# Power.net
KiCad netlist of a schematic drawn in Altium Designer
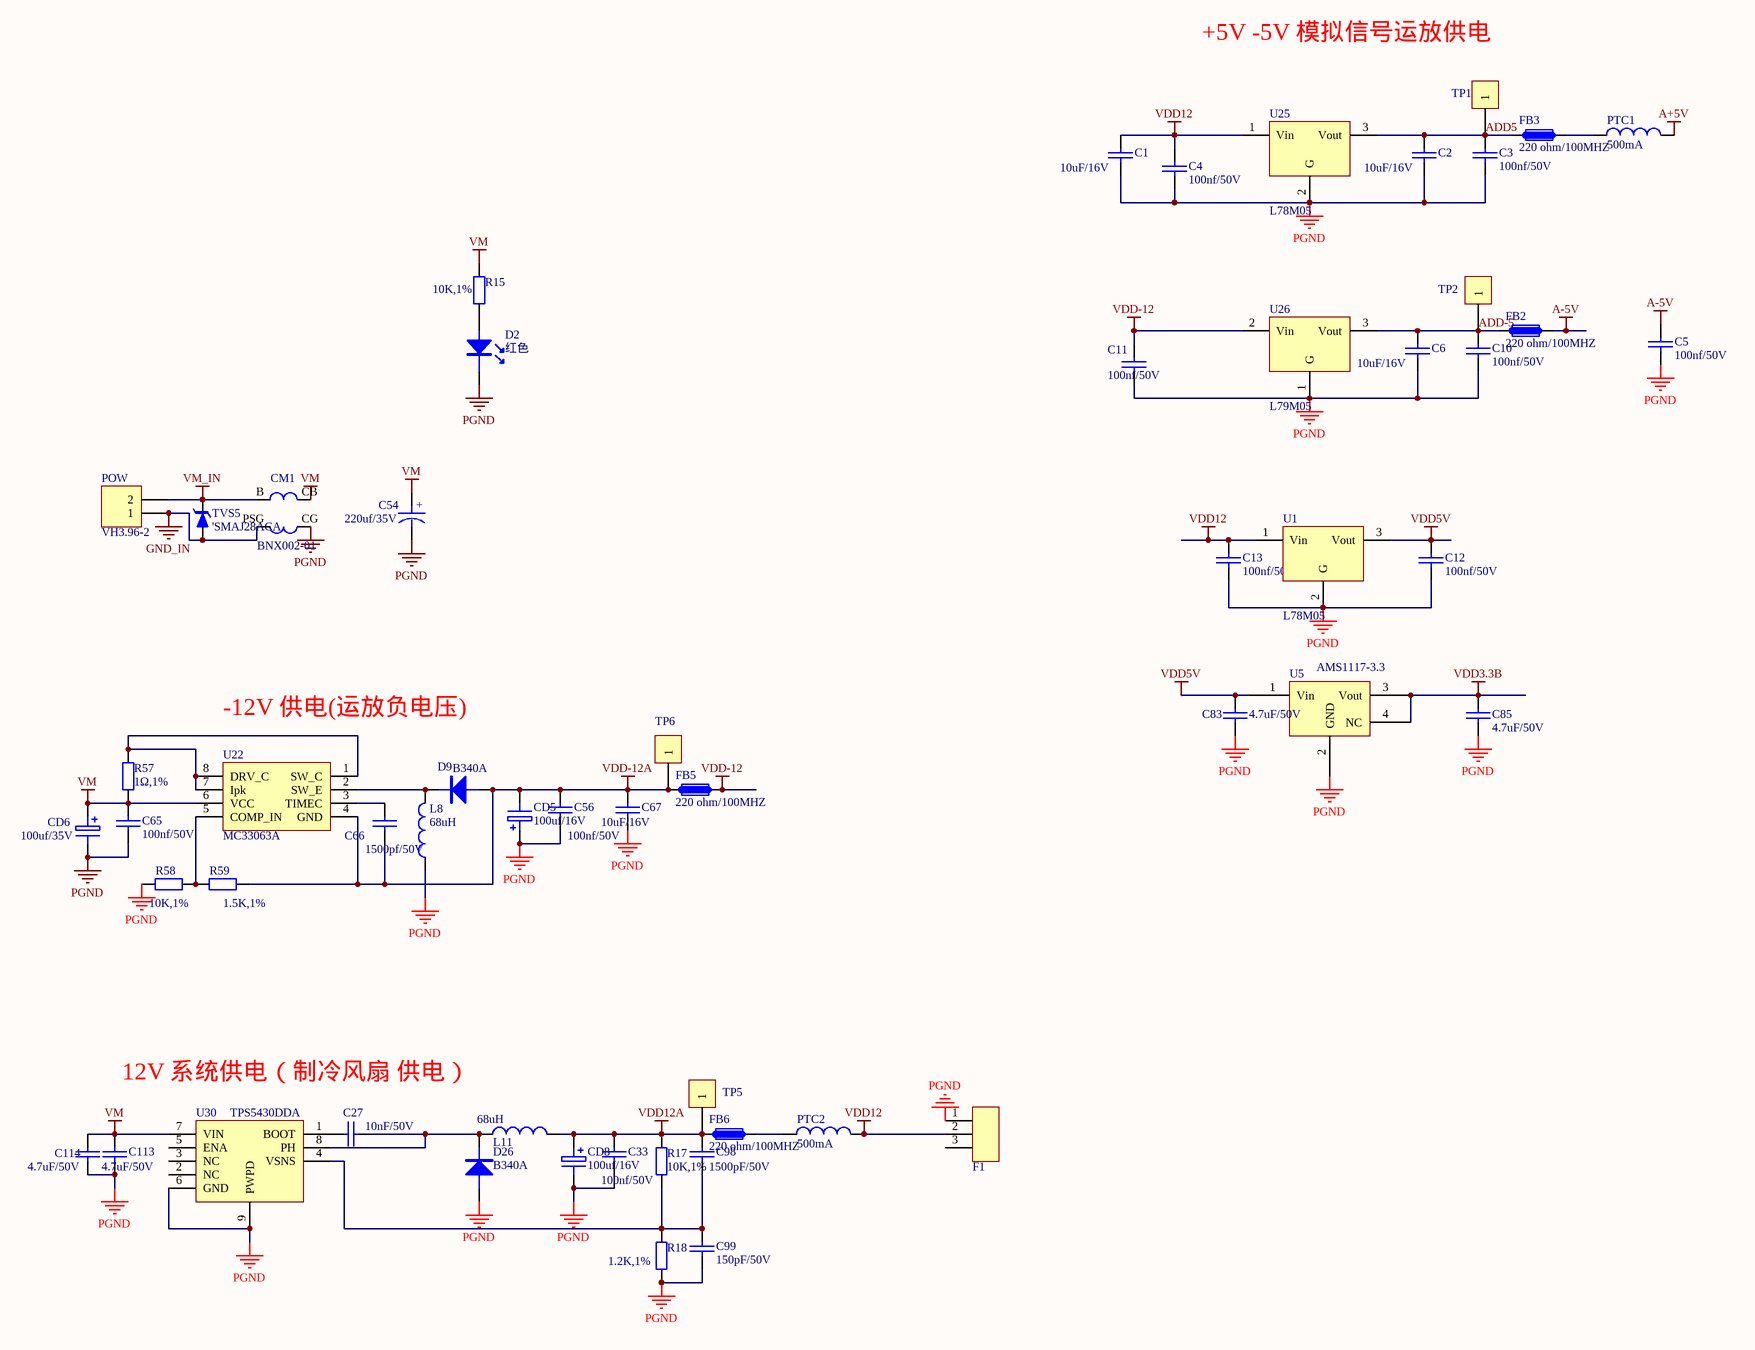
[diagram p0: Power.SchDoc]

(export (version "E")
  (design (tool "Eeschema 10.0.6"))
  (components
    (comp (ref "C1")
      (value "10uF/16V")
      (footprint "1206")
      (description "Capacitor")
      (libsource (lib "DiscreteCom") (part "CAP"))
    )
    (comp (ref "C2")
      (value "10uF/16V")
      (footprint "1206")
      (description "Capacitor")
      (libsource (lib "DiscreteCom") (part "CAP"))
    )
    (comp (ref "C3")
      (value "100nf/50V")
      (footprint "0805")
      (description "Capacitor")
      (libsource (lib "*") (part "CAP"))
    )
    (comp (ref "C4")
      (value "100nf/50V")
      (footprint "0805")
      (description "Capacitor")
      (libsource (lib "*") (part "CAP"))
    )
    (comp (ref "C5")
      (value "100nf/50V")
      (footprint "GeneralPcblib V0.1:0805")
      (description "Capacitor")
      (libsource (lib "General") (part "CAP"))
    )
    (comp (ref "C6")
      (value "10uF/16V")
      (footprint "1206")
      (description "Capacitor")
      (libsource (lib "DiscreteCom") (part "CAP"))
    )
    (comp (ref "C10")
      (value "100nf/50V")
      (footprint "0805")
      (description "Capacitor")
      (libsource (lib "*") (part "CAP"))
    )
    (comp (ref "C11")
      (value "100nf/50V")
      (footprint "0805")
      (description "Capacitor")
      (libsource (lib "*") (part "CAP"))
    )
    (comp (ref "C12")
      (value "100nf/50V")
      (footprint "0805")
      (description "Capacitor")
      (libsource (lib "*") (part "CAP"))
    )
    (comp (ref "C13")
      (value "100nf/50V")
      (footprint "0805")
      (description "Capacitor")
      (libsource (lib "*") (part "CAP"))
    )
    (comp (ref "C27")
      (value "10nF/50V")
      (footprint "0805")
      (description "Capacitor")
      (libsource (lib "DiscreteCom") (part "CAP"))
    )
    (comp (ref "C33")
      (value "100nf/50V")
      (footprint "0805")
      (description "Capacitor")
      (libsource (lib "DiscreteCom") (part "CAP"))
    )
    (comp (ref "C54")
      (value "220uf/35V")
      (footprint "CX8*10.5")
      (description "Capacitor")
      (libsource (lib "General") (part "CAPACITOR POL"))
    )
    (comp (ref "C56")
      (value "100nf/50V")
      (footprint "0805")
      (description "Capacitor")
      (libsource (lib "DiscreteCom") (part "CAP"))
    )
    (comp (ref "C65")
      (value "100nf/50V")
      (footprint "0805")
      (description "Capacitor")
      (libsource (lib "DiscreteCom") (part "CAP"))
    )
    (comp (ref "C66")
      (value "1500pf/50V")
      (footprint "0805")
      (description "Capacitor")
      (libsource (lib "DiscreteCom") (part "CAP"))
    )
    (comp (ref "C67")
      (value "10uF/16V")
      (footprint "GeneralPcblib V0.1:1206")
      (description "Capacitor")
      (libsource (lib "General") (part "CAP"))
    )
    (comp (ref "C83")
      (value "4.7uF/50V")
      (footprint "1206")
      (description "Capacitor")
      (libsource (lib "DiscreteCom") (part "CAP"))
    )
    (comp (ref "C85")
      (value "4.7uF/50V")
      (footprint "1206")
      (description "Capacitor")
      (libsource (lib "DiscreteCom") (part "CAP"))
    )
    (comp (ref "C98")
      (value "1500pF/50V")
      (footprint "0805")
      (description "Capacitor")
      (libsource (lib "DiscreteCom") (part "CAP"))
    )
    (comp (ref "C99")
      (value "150pF/50V")
      (footprint "0805")
      (description "Capacitor")
      (libsource (lib "DiscreteCom") (part "CAP"))
    )
    (comp (ref "C113")
      (value "4.7uF/50V")
      (footprint "1206")
      (description "Capacitor")
      (libsource (lib "DiscreteCom") (part "CAP"))
    )
    (comp (ref "C114")
      (value "4.7uF/50V")
      (footprint "1206")
      (description "Capacitor")
      (libsource (lib "DiscreteCom") (part "CAP"))
    )
    (comp (ref "CD5")
      (value "100uf/16V")
      (footprint "7343D")
      (description "Electrolytic Capacitor")
      (libsource (lib "DiscreteCom") (part "Capacitor Electrolytic"))
    )
    (comp (ref "CD6")
      (value "100uf/35V")
      (footprint "CX6.3*5.4")
      (description "Electrolytic Capacitor")
      (libsource (lib "DiscreteCom") (part "Capacitor Electrolytic"))
    )
    (comp (ref "CD8")
      (value "100uf/16V")
      (footprint "7343D")
      (description "Electrolytic Capacitor")
      (libsource (lib "DiscreteCom") (part "Capacitor Electrolytic"))
    )
    (comp (ref "CM1")
      (value "BNX002-01")
      (footprint "GeneralPcblib V0.1:BNX-002-01")
      (description "inductor")
      (libsource (lib "DiscreteCom") (part "EMIFIL-BNX"))
    )
    (comp (ref "D2")
      (value "红色")
      (footprint "LED_0805")
      (description "Led")
      (fields (field (name "Comment") "LED,Red"))
      (libsource (lib "DiscreteCom") (part "LED"))
    )
    (comp (ref "D9")
      (value "B340A")
      (footprint "SMA")
      (description "Diode")
      (libsource (lib "General") (part "DIODE"))
    )
    (comp (ref "D26")
      (value "B340A")
      (footprint "SMA")
      (description "Diode")
      (libsource (lib "General") (part "DIODE"))
    )
    (comp (ref "F1")
      (value "KF2510-3P")
      (footprint "KF2510-3")
      (description "KF2510-2.54-3P 针座")
      (libsource (lib "CON1") (part "KF2510-3P"))
    )
    (comp (ref "FB2")
      (value "220 ohm/100MHZ")
      (footprint "0805")
      (description "Ferrite Bead")
      (libsource (lib "DiscreteCom") (part "Ferrite Bead"))
    )
    (comp (ref "FB3")
      (value "220 ohm/100MHZ")
      (footprint "0805")
      (description "Ferrite Bead")
      (libsource (lib "DiscreteCom") (part "Ferrite Bead"))
    )
    (comp (ref "FB5")
      (value "220 ohm/100MHZ")
      (footprint "0805")
      (description "Ferrite Bead")
      (libsource (lib "DiscreteCom") (part "Ferrite Bead"))
    )
    (comp (ref "FB6")
      (value "220 ohm/100MHZ")
      (footprint "0805")
      (description "Ferrite Bead")
      (libsource (lib "DiscreteCom") (part "Ferrite Bead"))
    )
    (comp (ref "L8")
      (value "68uH")
      (footprint "INDUCTOR 6*6")
      (description "Inductor")
      (libsource (lib "General") (part "INDUCTOR"))
    )
    (comp (ref "L11")
      (value "68uH")
      (footprint "INDUCTOR 6*6")
      (description "Inductor")
      (libsource (lib "General") (part "INDUCTOR"))
    )
    (comp (ref "POW")
      (value "VH3.96-2")
      (footprint "VH3.96-2")
      (description "VH3.96 2P 插座")
      (fields (field (name "PUBLISHER") "Altium Limited"))
      (libsource (lib "CON1") (part "VH-2"))
    )
    (comp (ref "PTC1")
      (value "500mA")
      (footprint "GeneralPcblib V0.1:1210")
      (description "PTCC")
      (libsource (lib "DiscreteCom") (part "PTCC"))
    )
    (comp (ref "PTC2")
      (value "500mA")
      (footprint "GeneralPcblib V0.1:1210")
      (description "PTCC")
      (libsource (lib "DiscreteCom") (part "PTCC"))
    )
    (comp (ref "R15")
      (value "10K,1%")
      (footprint "0805")
      (description "Resistor")
      (fields (field (name "PUBLISHER") "Altium Limited"))
      (libsource (lib "") (part "Res2_2"))
    )
    (comp (ref "R17")
      (value "10K,1%")
      (footprint "0805")
      (description "Resistor")
      (fields (field (name "PUBLISHER") "Altium Limited"))
      (libsource (lib "General") (part "Res2"))
    )
    (comp (ref "R18")
      (value "1.2K,1%")
      (footprint "0805")
      (description "Resistor")
      (fields (field (name "PUBLISHER") "Altium Limited"))
      (libsource (lib "General") (part "Res2"))
    )
    (comp (ref "R57")
      (value "1Ω,1%")
      (footprint "GeneralPcblib V0.1:2512")
      (description "Resistor")
      (fields (field (name "PUBLISHER") "Altium Limited"))
      (libsource (lib "") (part "Res2_2"))
    )
    (comp (ref "R58")
      (value "10K,1%")
      (footprint "0805")
      (description "Resistor")
      (fields (field (name "PUBLISHER") "Altium Limited"))
      (libsource (lib "") (part "Res2_1"))
    )
    (comp (ref "R59")
      (value "1.5K,1%")
      (footprint "0805")
      (description "Resistor")
      (fields (field (name "PUBLISHER") "Altium Limited"))
      (libsource (lib "") (part "Res2_1"))
    )
    (comp (ref "TP1")
      (value "TP")
      (footprint "TP1")
      (description "Connector")
      (libsource (lib "General") (part "TP"))
    )
    (comp (ref "TP2")
      (value "TP")
      (footprint "TP1")
      (description "Connector")
      (libsource (lib "General") (part "TP"))
    )
    (comp (ref "TP5")
      (value "TP")
      (footprint "TP1")
      (description "Connector")
      (libsource (lib "General") (part "TP"))
    )
    (comp (ref "TP6")
      (value "TP")
      (footprint "TP1")
      (description "Connector")
      (libsource (lib "General") (part "TP"))
    )
    (comp (ref "TVS5")
      (value "'SMAJ28ACA")
      (footprint "GeneralPcblib V0.1:SMB")
      (libsource (lib "DiscreteCom") (part "TVS"))
    )
    (comp (ref "U1")
      (value "L78M05")
      (footprint "TO-252")
      (description "L78XX系列芯片")
      (libsource (lib "AnalogIC") (part "L78XX"))
    )
    (comp (ref "U5")
      (value "AMS1117-3.3")
      (footprint "SOT223S")
      (libsource (lib "General") (part "LM1117-33"))
    )
    (comp (ref "U22") (value "MC33063A") (footprint "SOIC8") (libsource (lib "General") (part "MC33063A")))
    (comp (ref "U25")
      (value "L78M05")
      (footprint "TO-252")
      (description "L78XX系列芯片")
      (libsource (lib "AnalogIC") (part "L78XX"))
    )
    (comp (ref "U26")
      (value "L79M05")
      (footprint "TO-252")
      (description "L79XX系列芯片")
      (libsource (lib "AnalogIC") (part "L79XX"))
    )
    (comp (ref "U30")
      (value "TPS5430DDA")
      (footprint "S0IC8-DDA")
      (libsource (lib "General") (part "TPS5430DDA"))
    )
  )
  (nets
    (net (code "1") (name "/ADD-5") (class "Default")
      (node (ref "C10") (pin "1") (pinfunction "1_1") (pintype "passive"))
      (node (ref "C6") (pin "1") (pinfunction "1_1") (pintype "passive"))
      (node (ref "FB2") (pin "1") (pinfunction "1_1") (pintype "passive"))
      (node (ref "TP2") (pin "1") (pinfunction "1_1") (pintype "passive"))
      (node (ref "U26") (pin "3") (pinfunction "Vout_3") (pintype "passive"))
    )
    (net (code "2") (name "/ADD5") (class "Default")
      (node (ref "C2") (pin "1") (pinfunction "1_1") (pintype "passive"))
      (node (ref "C3") (pin "1") (pinfunction "1_1") (pintype "passive"))
      (node (ref "FB3") (pin "1") (pinfunction "1_1") (pintype "passive"))
      (node (ref "TP1") (pin "1") (pinfunction "1_1") (pintype "passive"))
      (node (ref "U25") (pin "3") (pinfunction "Vout_3") (pintype "passive"))
    )
    (net (code "3") (name "A+5V") (class "Default")
      (node (ref "PTC1") (pin "2") (pinfunction "2_2") (pintype "passive"))
    )
    (net (code "4") (name "A-5V") (class "Default")
      (node (ref "C5") (pin "1") (pinfunction "1_1") (pintype "passive"))
      (node (ref "FB2") (pin "2") (pinfunction "2_2") (pintype "passive"))
    )
    (net (code "5") (name "GND_IN") (class "Default")
      (node (ref "CM1") (pin "PSG") (pinfunction "PSG_PSG") (pintype "passive"))
      (node (ref "POW") (pin "1") (pinfunction "1_1") (pintype "passive"))
      (node (ref "TVS5") (pin "A") (pinfunction "A_A") (pintype "passive"))
    )
    (net (code "6") (name "Net-(D2-PadA)") (class "Default")
      (node (ref "D2") (pin "A") (pinfunction "A_A") (pintype "passive"))
      (node (ref "R15") (pin "2") (pinfunction "2_2") (pintype "passive"))
    )
    (net (code "7") (name "Net-(FB3-Pad2)") (class "Default")
      (node (ref "FB3") (pin "2") (pinfunction "2_2") (pintype "passive"))
      (node (ref "PTC1") (pin "1") (pinfunction "1_1") (pintype "passive"))
    )
    (net (code "8") (name "Net-(FB6-Pad2)") (class "Default")
      (node (ref "FB6") (pin "2") (pinfunction "2_2") (pintype "passive"))
      (node (ref "PTC2") (pin "1") (pinfunction "1_1") (pintype "passive"))
    )
    (net (code "9") (name "Net-(U22-COMP_IN)") (class "Default")
      (node (ref "R58") (pin "1") (pinfunction "1_1") (pintype "passive"))
      (node (ref "R59") (pin "2") (pinfunction "2_2") (pintype "passive"))
      (node (ref "U22") (pin "5") (pinfunction "COMP_IN_5") (pintype "passive"))
    )
    (net (code "10") (name "Net-(U22-DRV_C)") (class "Default")
      (node (ref "R57") (pin "1") (pinfunction "1_1") (pintype "passive"))
      (node (ref "U22") (pin "1") (pinfunction "SW_C_1") (pintype "passive"))
      (node (ref "U22") (pin "7") (pinfunction "Ipk_7") (pintype "passive"))
      (node (ref "U22") (pin "8") (pinfunction "DRV_C_8") (pintype "passive"))
    )
    (net (code "11") (name "Net-(U22-SW_E)") (class "Default")
      (node (ref "D9") (pin "K") (pinfunction "K_K") (pintype "passive"))
      (node (ref "L8") (pin "2") (pinfunction "2_2") (pintype "passive"))
      (node (ref "U22") (pin "2") (pinfunction "SW_E_2") (pintype "passive"))
    )
    (net (code "12") (name "Net-(U22-TIMEC)") (class "Default")
      (node (ref "C66") (pin "1") (pinfunction "1_1") (pintype "passive"))
      (node (ref "U22") (pin "3") (pinfunction "TIMEC_3") (pintype "passive"))
    )
    (net (code "13") (name "Net-(U30-BOOT)") (class "Default")
      (node (ref "C27") (pin "1") (pinfunction "1_1") (pintype "passive"))
      (node (ref "U30") (pin "1") (pinfunction "BOOT_1") (pintype "passive"))
    )
    (net (code "14") (name "Net-(U30-PH)") (class "Default")
      (node (ref "C27") (pin "2") (pinfunction "2_2") (pintype "passive"))
      (node (ref "D26") (pin "K") (pinfunction "K_K") (pintype "passive"))
      (node (ref "L11") (pin "1") (pinfunction "1_1") (pintype "passive"))
      (node (ref "U30") (pin "8") (pinfunction "PH_8") (pintype "passive"))
    )
    (net (code "15") (name "Net-(U30-VSNS)") (class "Default")
      (node (ref "C98") (pin "1") (pinfunction "1_1") (pintype "passive"))
      (node (ref "C99") (pin "2") (pinfunction "2_2") (pintype "passive"))
      (node (ref "R17") (pin "1") (pinfunction "1_1") (pintype "passive"))
      (node (ref "R18") (pin "2") (pinfunction "2_2") (pintype "passive"))
      (node (ref "U30") (pin "4") (pinfunction "VSNS_4") (pintype "passive"))
    )
    (net (code "16") (name "PGND") (class "Default")
      (node (ref "C1") (pin "2") (pinfunction "2_2") (pintype "passive"))
      (node (ref "C10") (pin "2") (pinfunction "2_2") (pintype "passive"))
      (node (ref "C11") (pin "2") (pinfunction "2_2") (pintype "passive"))
      (node (ref "C113") (pin "2") (pinfunction "2_2") (pintype "passive"))
      (node (ref "C114") (pin "2") (pinfunction "2_2") (pintype "passive"))
      (node (ref "C12") (pin "2") (pinfunction "2_2") (pintype "passive"))
      (node (ref "C13") (pin "2") (pinfunction "2_2") (pintype "passive"))
      (node (ref "C2") (pin "2") (pinfunction "2_2") (pintype "passive"))
      (node (ref "C3") (pin "2") (pinfunction "2_2") (pintype "passive"))
      (node (ref "C33") (pin "2") (pinfunction "2_2") (pintype "passive"))
      (node (ref "C4") (pin "2") (pinfunction "2_2") (pintype "passive"))
      (node (ref "C5") (pin "2") (pinfunction "2_2") (pintype "passive"))
      (node (ref "C54") (pin "2") (pinfunction "2_2") (pintype "passive"))
      (node (ref "C56") (pin "2") (pinfunction "2_2") (pintype "passive"))
      (node (ref "C6") (pin "2") (pinfunction "2_2") (pintype "passive"))
      (node (ref "C65") (pin "2") (pinfunction "2_2") (pintype "passive"))
      (node (ref "C67") (pin "2") (pinfunction "2_2") (pintype "passive"))
      (node (ref "C83") (pin "2") (pinfunction "2_2") (pintype "passive"))
      (node (ref "C85") (pin "2") (pinfunction "2_2") (pintype "passive"))
      (node (ref "C99") (pin "1") (pinfunction "1_1") (pintype "passive"))
      (node (ref "CD5") (pin "1") (pinfunction "1_1") (pintype "passive"))
      (node (ref "CD6") (pin "2") (pinfunction "2_2") (pintype "passive"))
      (node (ref "CD8") (pin "2") (pinfunction "2_2") (pintype "passive"))
      (node (ref "CM1") (pin "CG") (pinfunction "CG_CG") (pintype "passive"))
      (node (ref "D2") (pin "K") (pinfunction "K_K") (pintype "passive"))
      (node (ref "D26") (pin "A") (pinfunction "A_A") (pintype "passive"))
      (node (ref "F1") (pin "1") (pintype "passive"))
      (node (ref "L8") (pin "1") (pinfunction "1_1") (pintype "passive"))
      (node (ref "R18") (pin "1") (pinfunction "1_1") (pintype "passive"))
      (node (ref "R58") (pin "2") (pinfunction "2_2") (pintype "passive"))
      (node (ref "U1") (pin "2") (pinfunction "G_2") (pintype "passive"))
      (node (ref "U25") (pin "2") (pinfunction "G_2") (pintype "passive"))
      (node (ref "U26") (pin "1") (pinfunction "G_1") (pintype "passive"))
      (node (ref "U30") (pin "6") (pinfunction "GND_6") (pintype "passive"))
      (node (ref "U30") (pin "9") (pinfunction "PWPD_9") (pintype "passive"))
      (node (ref "U5") (pin "2") (pinfunction "GND_2") (pintype "passive"))
    )
    (net (code "17") (name "VDD-12") (class "Default")
      (node (ref "C11") (pin "1") (pinfunction "1_1") (pintype "passive"))
      (node (ref "FB5") (pin "2") (pinfunction "2_2") (pintype "passive"))
      (node (ref "U26") (pin "2") (pinfunction "Vin_2") (pintype "passive"))
    )
    (net (code "18") (name "VDD-12A") (class "Default")
      (node (ref "C56") (pin "1") (pinfunction "1_1") (pintype "passive"))
      (node (ref "C66") (pin "2") (pinfunction "2_2") (pintype "passive"))
      (node (ref "C67") (pin "1") (pinfunction "1_1") (pintype "passive"))
      (node (ref "CD5") (pin "2") (pinfunction "2_2") (pintype "passive"))
      (node (ref "D9") (pin "A") (pinfunction "A_A") (pintype "passive"))
      (node (ref "FB5") (pin "1") (pinfunction "1_1") (pintype "passive"))
      (node (ref "R59") (pin "1") (pinfunction "1_1") (pintype "passive"))
      (node (ref "TP6") (pin "1") (pinfunction "1_1") (pintype "passive"))
      (node (ref "U22") (pin "4") (pinfunction "GND_4") (pintype "passive"))
    )
    (net (code "19") (name "VDD3.3B") (class "Default")
      (node (ref "C85") (pin "1") (pinfunction "1_1") (pintype "passive"))
      (node (ref "U5") (pin "3") (pinfunction "Vout_3") (pintype "passive"))
      (node (ref "U5") (pin "4") (pinfunction "NC_4") (pintype "passive"))
    )
    (net (code "20") (name "VDD5V") (class "Default")
      (node (ref "C12") (pin "1") (pinfunction "1_1") (pintype "passive"))
      (node (ref "C83") (pin "1") (pinfunction "1_1") (pintype "passive"))
      (node (ref "U1") (pin "3") (pinfunction "Vout_3") (pintype "passive"))
      (node (ref "U5") (pin "1") (pinfunction "Vin_1") (pintype "passive"))
    )
    (net (code "21") (name "VDD12") (class "Default")
      (node (ref "C1") (pin "1") (pinfunction "1_1") (pintype "passive"))
      (node (ref "C13") (pin "1") (pinfunction "1_1") (pintype "passive"))
      (node (ref "C4") (pin "1") (pinfunction "1_1") (pintype "passive"))
      (node (ref "F1") (pin "2") (pintype "passive"))
      (node (ref "PTC2") (pin "2") (pinfunction "2_2") (pintype "passive"))
      (node (ref "U1") (pin "1") (pinfunction "Vin_1") (pintype "passive"))
      (node (ref "U25") (pin "1") (pinfunction "Vin_1") (pintype "passive"))
    )
    (net (code "22") (name "VDD12A") (class "Default")
      (node (ref "C33") (pin "1") (pinfunction "1_1") (pintype "passive"))
      (node (ref "C98") (pin "2") (pinfunction "2_2") (pintype "passive"))
      (node (ref "CD8") (pin "1") (pinfunction "1_1") (pintype "passive"))
      (node (ref "FB6") (pin "1") (pinfunction "1_1") (pintype "passive"))
      (node (ref "L11") (pin "2") (pinfunction "2_2") (pintype "passive"))
      (node (ref "R17") (pin "2") (pinfunction "2_2") (pintype "passive"))
      (node (ref "TP5") (pin "1") (pinfunction "1_1") (pintype "passive"))
    )
    (net (code "23") (name "VM") (class "Default")
      (node (ref "C113") (pin "1") (pinfunction "1_1") (pintype "passive"))
      (node (ref "C114") (pin "1") (pinfunction "1_1") (pintype "passive"))
      (node (ref "C54") (pin "1") (pinfunction "1_1") (pintype "passive"))
      (node (ref "C65") (pin "1") (pinfunction "1_1") (pintype "passive"))
      (node (ref "CD6") (pin "1") (pinfunction "1_1") (pintype "passive"))
      (node (ref "CM1") (pin "CB") (pinfunction "CB_CB") (pintype "passive"))
      (node (ref "R15") (pin "1") (pinfunction "1_1") (pintype "passive"))
      (node (ref "R57") (pin "2") (pinfunction "2_2") (pintype "passive"))
      (node (ref "U22") (pin "6") (pinfunction "VCC_6") (pintype "passive"))
      (node (ref "U30") (pin "7") (pinfunction "VIN_7") (pintype "passive"))
    )
    (net (code "24") (name "VM_IN") (class "Default")
      (node (ref "CM1") (pin "B") (pinfunction "B_B") (pintype "passive"))
      (node (ref "POW") (pin "2") (pinfunction "2_2") (pintype "passive"))
      (node (ref "TVS5") (pin "K") (pinfunction "K_K") (pintype "passive"))
    )
    (net (code "25") (name "unconnected-(F1-Pad3)") (class "Default")
      (node (ref "F1") (pin "3") (pintype "passive"))
    )
    (net (code "26") (name "unconnected-(U30-ENA-Pad5)") (class "Default")
      (node (ref "U30") (pin "5") (pinfunction "ENA_5") (pintype "passive"))
    )
    (net (code "27") (name "unconnected-(U30-NC-Pad2)") (class "Default")
      (node (ref "U30") (pin "2") (pinfunction "NC_2") (pintype "passive"))
    )
    (net (code "28") (name "unconnected-(U30-NC-Pad3)") (class "Default")
      (node (ref "U30") (pin "3") (pinfunction "NC_3") (pintype "passive"))
    )
  )
)
